# 16chADXIAO.net
KiCad netlist of a schematic drawn in EAGLE
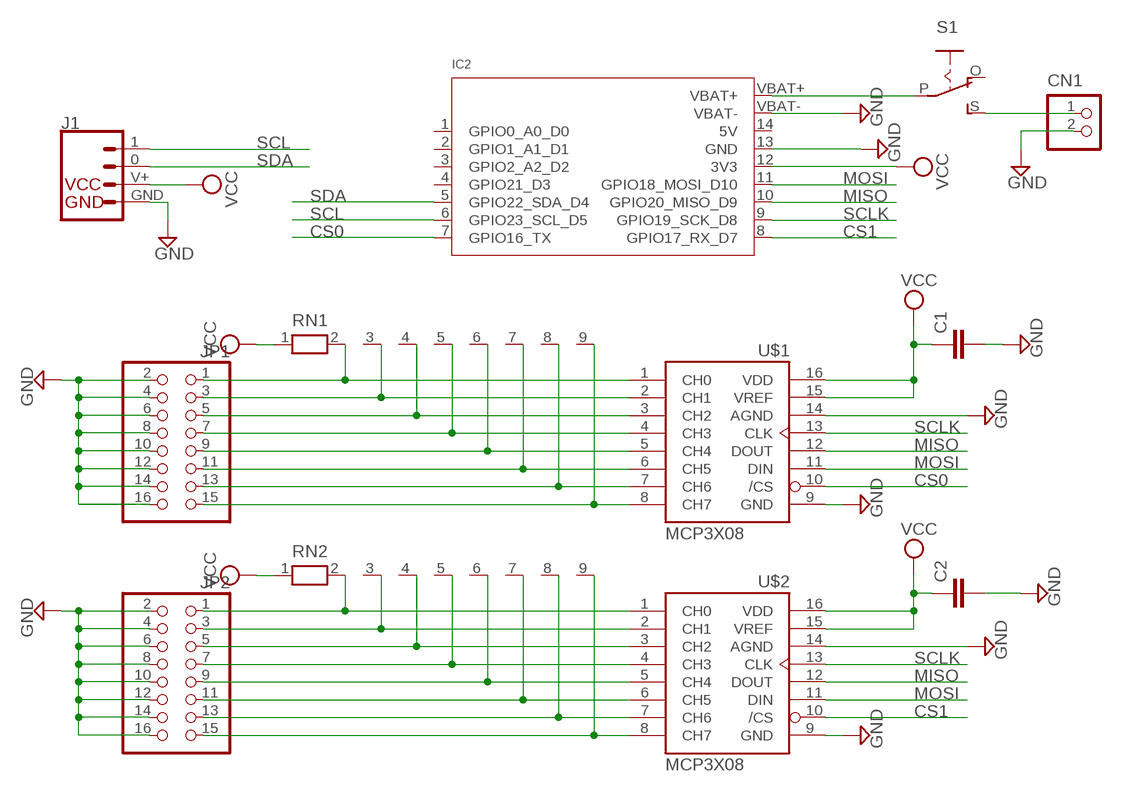
[diagram p0: schematic, sheet 1]

(export (version "E")
  (design (tool "Eeschema 10.0.6"))
  (components
    (comp (ref "C1")
      (value "C-EUC0805")
      (footprint "eagle-import:C0805")
      (libsource (lib "eagle-import") (part "C-EUC0805"))
    )
    (comp (ref "C2")
      (value "C-EUC0805")
      (footprint "eagle-import:C0805")
      (libsource (lib "eagle-import") (part "C-EUC0805"))
    )
    (comp (ref "CN1")
      (value "B2B-PH-K-S")
      (footprint "eagle-import:B2B-PH-K-S")
      (libsource (lib "eagle-import") (part "B2B-PH-K-S"))
    )
    (comp (ref "IC2")
      (value "MOUDLE-XIAO-ESO32C6")
      (footprint "eagle-import:XIAO-ESP32C6")
      (libsource (lib "eagle-import") (part "MOUDLE-XIAO-ESO32C6"))
    )
    (comp (ref "J1")
      (value "4P-2.0")
      (footprint "eagle-import:HW4-2.0-90D")
      (libsource (lib "eagle-import") (part "GROVE-CONNECTOR-DIP90D"))
    )
    (comp (ref "JP1")
      (value "PINHD-2X8/90")
      (footprint "eagle-import:2X08_90")
      (libsource (lib "eagle-import") (part "PINHD-2X8/90"))
    )
    (comp (ref "JP2")
      (value "PINHD-2X8/90")
      (footprint "eagle-import:2X08_90")
      (libsource (lib "eagle-import") (part "PINHD-2X8/90"))
    )
    (comp (ref "RN1")
      (value "RN08")
      (footprint "eagle-import:RN-9")
      (libsource (lib "eagle-import") (part "RN08"))
    )
    (comp (ref "RN2")
      (value "RN08")
      (footprint "eagle-import:RN-9")
      (libsource (lib "eagle-import") (part "RN08"))
    )
    (comp (ref "S1")
      (value "EG1218S")
      (footprint "eagle-import:EG1218")
      (libsource (lib "eagle-import") (part "EG1218S"))
    )
    (comp (ref "U$1")
      (value "MCP3X08")
      (footprint "eagle-import:SO16")
      (libsource (lib "eagle-import") (part "MCP3X08"))
    )
    (comp (ref "U$2")
      (value "MCP3X08")
      (footprint "eagle-import:SO16")
      (libsource (lib "eagle-import") (part "MCP3X08"))
    )
  )
  (nets
    (net (code "1") (name "/CS0") (class "Default")
      (node (ref "IC2") (pin "7") (pinfunction "GPIO16_TX_7") (pintype "bidirectional"))
      (node (ref "U$1") (pin "10") (pinfunction "/CS_10") (pintype "input"))
    )
    (net (code "2") (name "/CS1") (class "Default")
      (node (ref "IC2") (pin "8") (pinfunction "GPIO17_RX_D7_8") (pintype "bidirectional"))
      (node (ref "U$2") (pin "10") (pinfunction "/CS_10") (pintype "input"))
    )
    (net (code "3") (name "/MISO") (class "Default")
      (node (ref "IC2") (pin "10") (pinfunction "GPIO20_MISO_D9_10") (pintype "bidirectional"))
      (node (ref "U$1") (pin "12") (pinfunction "DOUT_12") (pintype "output"))
      (node (ref "U$2") (pin "12") (pinfunction "DOUT_12") (pintype "output"))
    )
    (net (code "4") (name "/MOSI") (class "Default")
      (node (ref "IC2") (pin "11") (pinfunction "GPIO18_MOSI_D10_11") (pintype "bidirectional"))
      (node (ref "U$1") (pin "11") (pinfunction "DIN_11") (pintype "input"))
      (node (ref "U$2") (pin "11") (pinfunction "DIN_11") (pintype "input"))
    )
    (net (code "5") (name "/SCL") (class "Default")
      (node (ref "IC2") (pin "6") (pinfunction "GPIO23_SCL_D5_6") (pintype "bidirectional"))
      (node (ref "J1") (pin "1") (pinfunction "4_1") (pintype "passive"))
    )
    (net (code "6") (name "/SCLK") (class "Default")
      (node (ref "IC2") (pin "9") (pinfunction "GPIO19_SCK_D8_9") (pintype "bidirectional"))
      (node (ref "U$1") (pin "13") (pinfunction "CLK_13") (pintype "input"))
      (node (ref "U$2") (pin "13") (pinfunction "CLK_13") (pintype "input"))
    )
    (net (code "7") (name "/SDA") (class "Default")
      (node (ref "IC2") (pin "5") (pinfunction "GPIO22_SDA_D4_5") (pintype "bidirectional"))
      (node (ref "J1") (pin "0") (pinfunction "3_0") (pintype "passive"))
    )
    (net (code "8") (name "GND") (class "Default")
      (node (ref "C1") (pin "2") (pinfunction "2_2") (pintype "passive"))
      (node (ref "C2") (pin "2") (pinfunction "2_2") (pintype "passive"))
      (node (ref "CN1") (pin "2") (pinfunction "2_2") (pintype "passive"))
      (node (ref "IC2") (pin "13") (pinfunction "GND_13") (pintype "bidirectional"))
      (node (ref "IC2") (pin "VBAT-") (pinfunction "VBAT-_VBAT-") (pintype "bidirectional"))
      (node (ref "J1") (pin "GND") (pinfunction "GND_GND") (pintype "power_in"))
      (node (ref "JP1") (pin "10") (pinfunction "10_10") (pintype "passive"))
      (node (ref "JP1") (pin "12") (pinfunction "12_12") (pintype "passive"))
      (node (ref "JP1") (pin "14") (pinfunction "14_14") (pintype "passive"))
      (node (ref "JP1") (pin "16") (pinfunction "16_16") (pintype "passive"))
      (node (ref "JP1") (pin "2") (pinfunction "2_2") (pintype "passive"))
      (node (ref "JP1") (pin "4") (pinfunction "4_4") (pintype "passive"))
      (node (ref "JP1") (pin "6") (pinfunction "6_6") (pintype "passive"))
      (node (ref "JP1") (pin "8") (pinfunction "8_8") (pintype "passive"))
      (node (ref "JP2") (pin "10") (pinfunction "10_10") (pintype "passive"))
      (node (ref "JP2") (pin "12") (pinfunction "12_12") (pintype "passive"))
      (node (ref "JP2") (pin "14") (pinfunction "14_14") (pintype "passive"))
      (node (ref "JP2") (pin "16") (pinfunction "16_16") (pintype "passive"))
      (node (ref "JP2") (pin "2") (pinfunction "2_2") (pintype "passive"))
      (node (ref "JP2") (pin "4") (pinfunction "4_4") (pintype "passive"))
      (node (ref "JP2") (pin "6") (pinfunction "6_6") (pintype "passive"))
      (node (ref "JP2") (pin "8") (pinfunction "8_8") (pintype "passive"))
      (node (ref "U$1") (pin "14") (pinfunction "AGND_14") (pintype "power_in"))
      (node (ref "U$1") (pin "9") (pinfunction "GND_9") (pintype "power_in"))
      (node (ref "U$2") (pin "14") (pinfunction "AGND_14") (pintype "power_in"))
      (node (ref "U$2") (pin "9") (pinfunction "GND_9") (pintype "power_in"))
    )
    (net (code "9") (name "Net-(CN1-Pad1)") (class "Default")
      (node (ref "CN1") (pin "1") (pinfunction "1_1") (pintype "passive"))
      (node (ref "S1") (pin "S") (pinfunction "S_S") (pintype "passive"))
    )
    (net (code "10") (name "Net-(IC2-PadVBAT+)") (class "Default")
      (node (ref "IC2") (pin "VBAT+") (pinfunction "VBAT+_VBAT+") (pintype "bidirectional"))
      (node (ref "S1") (pin "P") (pinfunction "P_P") (pintype "passive"))
    )
    (net (code "11") (name "Net-(U$1-CH0)") (class "Default")
      (node (ref "JP1") (pin "1") (pinfunction "1_1") (pintype "passive"))
      (node (ref "RN1") (pin "2") (pinfunction "2_2") (pintype "passive"))
      (node (ref "U$1") (pin "1") (pinfunction "CH0_1") (pintype "input"))
    )
    (net (code "12") (name "Net-(U$1-CH1)") (class "Default")
      (node (ref "JP1") (pin "3") (pinfunction "3_3") (pintype "passive"))
      (node (ref "RN1") (pin "3") (pinfunction "3_3") (pintype "passive"))
      (node (ref "U$1") (pin "2") (pinfunction "CH1_2") (pintype "input"))
    )
    (net (code "13") (name "Net-(U$1-CH2)") (class "Default")
      (node (ref "JP1") (pin "5") (pinfunction "5_5") (pintype "passive"))
      (node (ref "RN1") (pin "4") (pinfunction "4_4") (pintype "passive"))
      (node (ref "U$1") (pin "3") (pinfunction "CH2_3") (pintype "input"))
    )
    (net (code "14") (name "Net-(U$1-CH3)") (class "Default")
      (node (ref "JP1") (pin "7") (pinfunction "7_7") (pintype "passive"))
      (node (ref "RN1") (pin "5") (pinfunction "5_5") (pintype "passive"))
      (node (ref "U$1") (pin "4") (pinfunction "CH3_4") (pintype "input"))
    )
    (net (code "15") (name "Net-(U$1-CH4)") (class "Default")
      (node (ref "JP1") (pin "9") (pinfunction "9_9") (pintype "passive"))
      (node (ref "RN1") (pin "6") (pinfunction "6_6") (pintype "passive"))
      (node (ref "U$1") (pin "5") (pinfunction "CH4_5") (pintype "input"))
    )
    (net (code "16") (name "Net-(U$1-CH5)") (class "Default")
      (node (ref "JP1") (pin "11") (pinfunction "11_11") (pintype "passive"))
      (node (ref "RN1") (pin "7") (pinfunction "7_7") (pintype "passive"))
      (node (ref "U$1") (pin "6") (pinfunction "CH5_6") (pintype "input"))
    )
    (net (code "17") (name "Net-(U$1-CH6)") (class "Default")
      (node (ref "JP1") (pin "13") (pinfunction "13_13") (pintype "passive"))
      (node (ref "RN1") (pin "8") (pinfunction "8_8") (pintype "passive"))
      (node (ref "U$1") (pin "7") (pinfunction "CH6_7") (pintype "input"))
    )
    (net (code "18") (name "Net-(U$1-CH7)") (class "Default")
      (node (ref "JP1") (pin "15") (pinfunction "15_15") (pintype "passive"))
      (node (ref "RN1") (pin "9") (pinfunction "9_9") (pintype "passive"))
      (node (ref "U$1") (pin "8") (pinfunction "CH7_8") (pintype "input"))
    )
    (net (code "19") (name "Net-(U$2-CH0)") (class "Default")
      (node (ref "JP2") (pin "1") (pinfunction "1_1") (pintype "passive"))
      (node (ref "RN2") (pin "2") (pinfunction "2_2") (pintype "passive"))
      (node (ref "U$2") (pin "1") (pinfunction "CH0_1") (pintype "input"))
    )
    (net (code "20") (name "Net-(U$2-CH1)") (class "Default")
      (node (ref "JP2") (pin "3") (pinfunction "3_3") (pintype "passive"))
      (node (ref "RN2") (pin "3") (pinfunction "3_3") (pintype "passive"))
      (node (ref "U$2") (pin "2") (pinfunction "CH1_2") (pintype "input"))
    )
    (net (code "21") (name "Net-(U$2-CH2)") (class "Default")
      (node (ref "JP2") (pin "5") (pinfunction "5_5") (pintype "passive"))
      (node (ref "RN2") (pin "4") (pinfunction "4_4") (pintype "passive"))
      (node (ref "U$2") (pin "3") (pinfunction "CH2_3") (pintype "input"))
    )
    (net (code "22") (name "Net-(U$2-CH3)") (class "Default")
      (node (ref "JP2") (pin "7") (pinfunction "7_7") (pintype "passive"))
      (node (ref "RN2") (pin "5") (pinfunction "5_5") (pintype "passive"))
      (node (ref "U$2") (pin "4") (pinfunction "CH3_4") (pintype "input"))
    )
    (net (code "23") (name "Net-(U$2-CH4)") (class "Default")
      (node (ref "JP2") (pin "9") (pinfunction "9_9") (pintype "passive"))
      (node (ref "RN2") (pin "6") (pinfunction "6_6") (pintype "passive"))
      (node (ref "U$2") (pin "5") (pinfunction "CH4_5") (pintype "input"))
    )
    (net (code "24") (name "Net-(U$2-CH5)") (class "Default")
      (node (ref "JP2") (pin "11") (pinfunction "11_11") (pintype "passive"))
      (node (ref "RN2") (pin "7") (pinfunction "7_7") (pintype "passive"))
      (node (ref "U$2") (pin "6") (pinfunction "CH5_6") (pintype "input"))
    )
    (net (code "25") (name "Net-(U$2-CH6)") (class "Default")
      (node (ref "JP2") (pin "13") (pinfunction "13_13") (pintype "passive"))
      (node (ref "RN2") (pin "8") (pinfunction "8_8") (pintype "passive"))
      (node (ref "U$2") (pin "7") (pinfunction "CH6_7") (pintype "input"))
    )
    (net (code "26") (name "Net-(U$2-CH7)") (class "Default")
      (node (ref "JP2") (pin "15") (pinfunction "15_15") (pintype "passive"))
      (node (ref "RN2") (pin "9") (pinfunction "9_9") (pintype "passive"))
      (node (ref "U$2") (pin "8") (pinfunction "CH7_8") (pintype "input"))
    )
    (net (code "27") (name "VCC") (class "Default")
      (node (ref "C1") (pin "1") (pinfunction "1_1") (pintype "passive"))
      (node (ref "C2") (pin "1") (pinfunction "1_1") (pintype "passive"))
      (node (ref "IC2") (pin "12") (pinfunction "3V3_12") (pintype "bidirectional"))
      (node (ref "J1") (pin "V+") (pinfunction "VCC_V+") (pintype "power_in"))
      (node (ref "RN1") (pin "1") (pinfunction "1_1") (pintype "passive"))
      (node (ref "RN2") (pin "1") (pinfunction "1_1") (pintype "passive"))
      (node (ref "U$1") (pin "15") (pinfunction "VREF_15") (pintype "input"))
      (node (ref "U$1") (pin "16") (pinfunction "VDD_16") (pintype "power_in"))
      (node (ref "U$2") (pin "15") (pinfunction "VREF_15") (pintype "input"))
      (node (ref "U$2") (pin "16") (pinfunction "VDD_16") (pintype "power_in"))
    )
    (net (code "28") (name "unconnected-(IC2-5V-Pad14)") (class "Default")
      (node (ref "IC2") (pin "14") (pinfunction "5V_14") (pintype "bidirectional"))
    )
    (net (code "29") (name "unconnected-(IC2-GPIO0_A0_D0-Pad1)") (class "Default")
      (node (ref "IC2") (pin "1") (pinfunction "GPIO0_A0_D0_1") (pintype "bidirectional"))
    )
    (net (code "30") (name "unconnected-(IC2-GPIO1_A1_D1-Pad2)") (class "Default")
      (node (ref "IC2") (pin "2") (pinfunction "GPIO1_A1_D1_2") (pintype "bidirectional"))
    )
    (net (code "31") (name "unconnected-(IC2-GPIO2_A2_D2-Pad3)") (class "Default")
      (node (ref "IC2") (pin "3") (pinfunction "GPIO2_A2_D2_3") (pintype "bidirectional"))
    )
    (net (code "32") (name "unconnected-(IC2-GPIO21_D3-Pad4)") (class "Default")
      (node (ref "IC2") (pin "4") (pinfunction "GPIO21_D3_4") (pintype "bidirectional"))
    )
    (net (code "33") (name "unconnected-(S1-PadO)") (class "Default")
      (node (ref "S1") (pin "O") (pinfunction "O_O") (pintype "passive"))
    )
  )
)
